# Rs232IC.net
KiCad netlist of a schematic drawn in Altium Designer
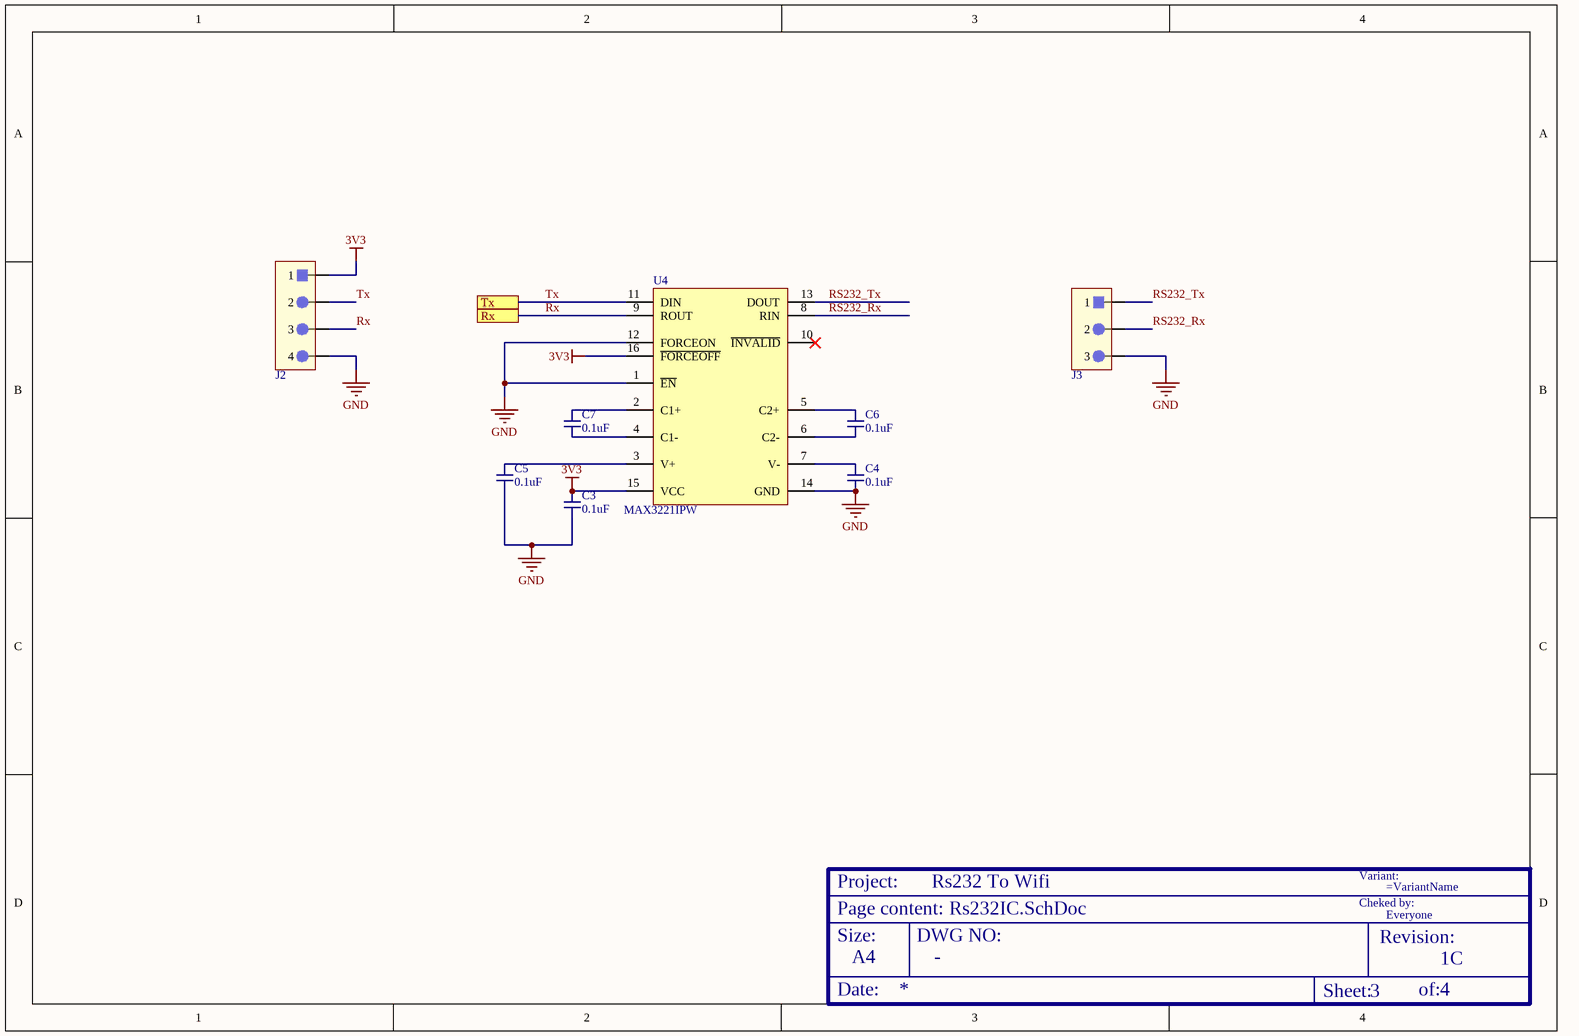
[diagram p0: Rs232IC.SchDoc]

(export (version "E")
  (design (tool "Eeschema 10.0.6"))
  (components
    (comp (ref "C3")
      (value "0.1uF")
      (footprint "0603C")
      (description "Ceramic Capacitor")
      (libsource (lib "General_Libs") (part "CC"))
    )
    (comp (ref "C4")
      (value "0.1uF")
      (footprint "0603C")
      (description "Ceramic Capacitor")
      (libsource (lib "General_Libs") (part "CC"))
    )
    (comp (ref "C5")
      (value "0.1uF")
      (footprint "0603C")
      (description "Ceramic Capacitor")
      (libsource (lib "General_Libs") (part "CC"))
    )
    (comp (ref "C6")
      (value "0.1uF")
      (footprint "0603C")
      (description "Ceramic Capacitor")
      (libsource (lib "General_Libs") (part "CC"))
    )
    (comp (ref "C7")
      (value "0.1uF")
      (footprint "0603C")
      (description "Ceramic Capacitor")
      (libsource (lib "General_Libs") (part "CC"))
    )
    (comp (ref "J2")
      (value "Conector")
      (footprint "61300411121")
      (description "Conector 4 pins")
      (libsource (lib "General_Libs") (part "Conector 4 pins"))
    )
    (comp (ref "J3")
      (value "Conector")
      (footprint "61300311121")
      (description "Conector 3 pins")
      (libsource (lib "General_Libs") (part "Conector 3 pins"))
    )
    (comp (ref "U4")
      (value "MAX3221IPW")
      (footprint "TI-PW16_M")
      (fields (field (name "Comment") "RS232 Serie CI"))
      (libsource (lib "General_Libs") (part "MAX3221IPW"))
    )
  )
  (nets
    (net (code "1") (name "/RS232_Rx") (class "Default")
      (node (ref "J3") (pin "2") (pinfunction "2_2") (pintype "passive"))
      (node (ref "U4") (pin "8") (pinfunction "RIN_8") (pintype "passive"))
    )
    (net (code "2") (name "/RS232_Tx") (class "Default")
      (node (ref "J3") (pin "1") (pinfunction "1_1") (pintype "passive"))
      (node (ref "U4") (pin "13") (pinfunction "DOUT_13") (pintype "tri_state"))
    )
    (net (code "3") (name "/Rx") (class "Default")
      (node (ref "J2") (pin "3") (pinfunction "3_3") (pintype "passive"))
      (node (ref "U4") (pin "9") (pinfunction "ROUT_9") (pintype "passive"))
    )
    (net (code "4") (name "/Tx") (class "Default")
      (node (ref "J2") (pin "2") (pinfunction "2_2") (pintype "passive"))
      (node (ref "U4") (pin "11") (pinfunction "DIN_11") (pintype "passive"))
    )
    (net (code "5") (name "3V3") (class "Default")
      (node (ref "C3") (pin "1") (pinfunction "1_1") (pintype "passive"))
      (node (ref "J2") (pin "1") (pinfunction "1_1") (pintype "passive"))
      (node (ref "U4") (pin "15") (pinfunction "VCC_15") (pintype "power_in"))
      (node (ref "U4") (pin "16") (pinfunction "~{FORCEOFF}_16") (pintype "passive"))
    )
    (net (code "6") (name "GND") (class "Default")
      (node (ref "C3") (pin "2") (pinfunction "2_2") (pintype "passive"))
      (node (ref "C4") (pin "2") (pinfunction "2_2") (pintype "passive"))
      (node (ref "C5") (pin "2") (pinfunction "2_2") (pintype "passive"))
      (node (ref "J2") (pin "4") (pinfunction "4_4") (pintype "passive"))
      (node (ref "J3") (pin "3") (pinfunction "3_3") (pintype "passive"))
      (node (ref "U4") (pin "1") (pinfunction "~{EN}_1") (pintype "passive"))
      (node (ref "U4") (pin "12") (pinfunction "FORCEON_12") (pintype "passive"))
      (node (ref "U4") (pin "14") (pinfunction "GND_14") (pintype "power_in"))
    )
    (net (code "7") (name "Net-(U4-C1+)") (class "Default")
      (node (ref "C7") (pin "1") (pinfunction "1_1") (pintype "passive"))
      (node (ref "U4") (pin "2") (pinfunction "C1+_2") (pintype "passive"))
    )
    (net (code "8") (name "Net-(U4-C1-)") (class "Default")
      (node (ref "C7") (pin "2") (pinfunction "2_2") (pintype "passive"))
      (node (ref "U4") (pin "4") (pinfunction "C1-_4") (pintype "passive"))
    )
    (net (code "9") (name "Net-(U4-C2+)") (class "Default")
      (node (ref "C6") (pin "1") (pinfunction "1_1") (pintype "passive"))
      (node (ref "U4") (pin "5") (pinfunction "C2+_5") (pintype "passive"))
    )
    (net (code "10") (name "Net-(U4-C2-)") (class "Default")
      (node (ref "C6") (pin "2") (pinfunction "2_2") (pintype "passive"))
      (node (ref "U4") (pin "6") (pinfunction "C2-_6") (pintype "passive"))
    )
    (net (code "11") (name "Net-(U4-V+)") (class "Default")
      (node (ref "C5") (pin "1") (pinfunction "1_1") (pintype "passive"))
      (node (ref "U4") (pin "3") (pinfunction "V+_3") (pintype "power_in"))
    )
    (net (code "12") (name "Net-(U4-V-)") (class "Default")
      (node (ref "C4") (pin "1") (pinfunction "1_1") (pintype "passive"))
      (node (ref "U4") (pin "7") (pinfunction "V-_7") (pintype "power_in"))
    )
    (net (code "13") (name "unconnected-(U4-~{INVALID}-Pad10)") (class "Default")
      (node (ref "U4") (pin "10") (pinfunction "~{INVALID}_10") (pintype "passive+no_connect"))
    )
  )
)
